# MCU.net
KiCad netlist of a schematic drawn in Altium Designer
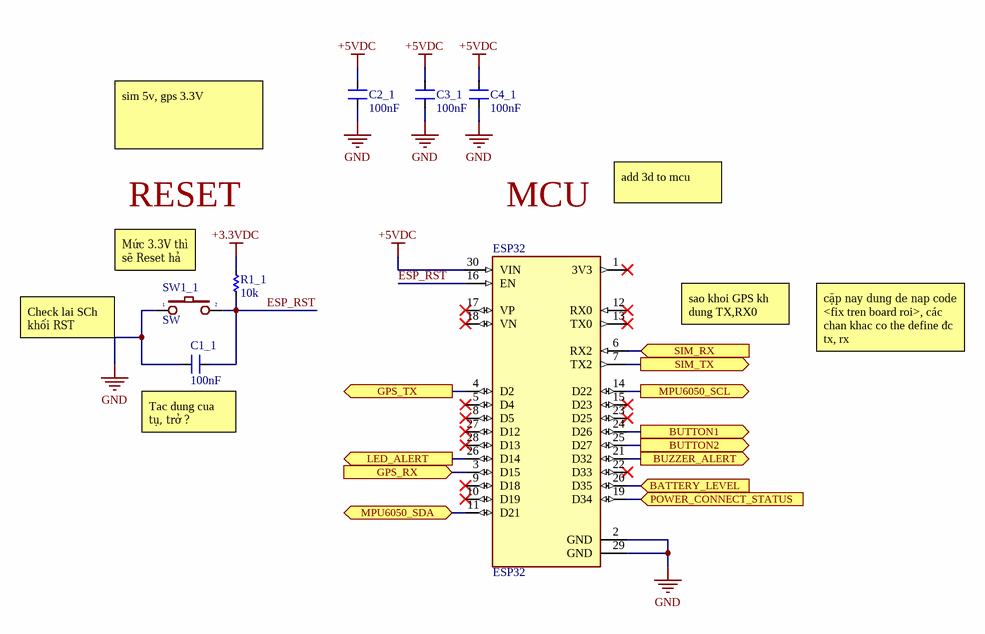
[diagram p0: MCU.SchDoc]

(export (version "E")
  (design (tool "Eeschema 10.0.6"))
  (components
    (comp (ref "C1_1")
      (value "100nF")
      (footprint "CN-SMD-0805")
      (libsource (lib "Altium Library") (part "CN"))
    )
    (comp (ref "C2_1")
      (value "100nF")
      (footprint "CN-SMD-0805")
      (libsource (lib "Altium Library") (part "CN"))
    )
    (comp (ref "C3_1")
      (value "100nF")
      (footprint "CN-SMD-0805")
      (libsource (lib "Altium Library") (part "CN"))
    )
    (comp (ref "C4_1")
      (value "100nF")
      (footprint "CN-SMD-0805")
      (libsource (lib "Altium Library") (part "CN"))
    )
    (comp (ref "ESP32")
      (value "ESP32")
      (footprint "MODULE_ESP32_DEVKIT_V1")
      (fields (field (name "MP") "ESP32-DEVKIT-V1"))
      (libsource (lib "GPS_LTE") (part "ESP32-DEVKIT-V1"))
    )
    (comp (ref "R1_1")
      (value "10k")
      (footprint "RES-SMD-0805")
      (description "Resistor")
      (fields
        (field (name "MANUFACTURER") "Generic Components")
        (field (name "PUBLISHER") "Altium Hobart Technology Centre")
      )
      (libsource (lib "Altium Library") (part "Res-SMD"))
    )
    (comp (ref "SW1_1")
      (value "SW")
      (footprint "SW1-DIP")
      (description "Switch button 2 pin")
      (libsource (lib "Altium Library") (part "SW2"))
    )
  )
  (nets
    (net (code "1") (name "+3.3VDC") (class "Default")
      (node (ref "R1_1") (pin "1") (pinfunction "1_1") (pintype "passive"))
    )
    (net (code "2") (name "+5VDC") (class "Default")
      (node (ref "C2_1") (pin "2") (pinfunction "2_2") (pintype "passive"))
      (node (ref "C3_1") (pin "2") (pinfunction "2_2") (pintype "passive"))
      (node (ref "C4_1") (pin "2") (pinfunction "2_2") (pintype "passive"))
      (node (ref "ESP32") (pin "30") (pinfunction "VIN_30") (pintype "input"))
    )
    (net (code "3") (name "/BATTERY_LEVEL") (class "Default")
      (node (ref "ESP32") (pin "20") (pinfunction "D35_20") (pintype "bidirectional"))
    )
    (net (code "4") (name "/BUTTON1") (class "Default")
      (node (ref "ESP32") (pin "24") (pinfunction "D26_24") (pintype "bidirectional"))
    )
    (net (code "5") (name "/BUTTON2") (class "Default")
      (node (ref "ESP32") (pin "25") (pinfunction "D27_25") (pintype "bidirectional"))
    )
    (net (code "6") (name "/BUZZER_ALERT") (class "Default")
      (node (ref "ESP32") (pin "21") (pinfunction "D32_21") (pintype "bidirectional"))
    )
    (net (code "7") (name "/ESP_RST") (class "Default")
      (node (ref "C1_1") (pin "2") (pinfunction "2_2") (pintype "passive"))
      (node (ref "ESP32") (pin "16") (pinfunction "EN_16") (pintype "input"))
      (node (ref "R1_1") (pin "2") (pinfunction "2_2") (pintype "passive"))
      (node (ref "SW1_1") (pin "2") (pinfunction "2_2") (pintype "passive"))
    )
    (net (code "8") (name "/GPS_RX") (class "Default")
      (node (ref "ESP32") (pin "3") (pinfunction "D15_3") (pintype "bidirectional"))
    )
    (net (code "9") (name "/GPS_TX") (class "Default")
      (node (ref "ESP32") (pin "4") (pinfunction "D2_4") (pintype "bidirectional"))
    )
    (net (code "10") (name "/LED_ALERT") (class "Default")
      (node (ref "ESP32") (pin "26") (pinfunction "D14_26") (pintype "bidirectional"))
    )
    (net (code "11") (name "/MPU6050_SCL") (class "Default")
      (node (ref "ESP32") (pin "14") (pinfunction "D22_14") (pintype "bidirectional"))
    )
    (net (code "12") (name "/MPU6050_SDA") (class "Default")
      (node (ref "ESP32") (pin "11") (pinfunction "D21_11") (pintype "bidirectional"))
    )
    (net (code "13") (name "/POWER_CONNECT_STATUS") (class "Default")
      (node (ref "ESP32") (pin "19") (pinfunction "D34_19") (pintype "bidirectional"))
    )
    (net (code "14") (name "/SIM_RX") (class "Default")
      (node (ref "ESP32") (pin "6") (pinfunction "RX2_6") (pintype "input"))
    )
    (net (code "15") (name "/SIM_TX") (class "Default")
      (node (ref "ESP32") (pin "7") (pinfunction "TX2_7") (pintype "output"))
    )
    (net (code "16") (name "GND") (class "Default")
      (node (ref "C1_1") (pin "1") (pinfunction "1_1") (pintype "passive"))
      (node (ref "C2_1") (pin "1") (pinfunction "1_1") (pintype "passive"))
      (node (ref "C3_1") (pin "1") (pinfunction "1_1") (pintype "passive"))
      (node (ref "C4_1") (pin "1") (pinfunction "1_1") (pintype "passive"))
      (node (ref "ESP32") (pin "2") (pinfunction "GND_2") (pintype "power_in"))
      (node (ref "ESP32") (pin "29") (pinfunction "GND_29") (pintype "power_in"))
      (node (ref "SW1_1") (pin "1") (pinfunction "1_1") (pintype "passive"))
    )
    (net (code "17") (name "unconnected-(ESP32-3V3-Pad1)") (class "Default")
      (node (ref "ESP32") (pin "1") (pinfunction "3V3_1") (pintype "output+no_connect"))
    )
    (net (code "18") (name "unconnected-(ESP32-D4-Pad5)") (class "Default")
      (node (ref "ESP32") (pin "5") (pinfunction "D4_5") (pintype "bidirectional+no_connect"))
    )
    (net (code "19") (name "unconnected-(ESP32-D5-Pad8)") (class "Default")
      (node (ref "ESP32") (pin "8") (pinfunction "D5_8") (pintype "bidirectional+no_connect"))
    )
    (net (code "20") (name "unconnected-(ESP32-D12-Pad27)") (class "Default")
      (node (ref "ESP32") (pin "27") (pinfunction "D12_27") (pintype "bidirectional+no_connect"))
    )
    (net (code "21") (name "unconnected-(ESP32-D13-Pad28)") (class "Default")
      (node (ref "ESP32") (pin "28") (pinfunction "D13_28") (pintype "bidirectional+no_connect"))
    )
    (net (code "22") (name "unconnected-(ESP32-D18-Pad9)") (class "Default")
      (node (ref "ESP32") (pin "9") (pinfunction "D18_9") (pintype "bidirectional+no_connect"))
    )
    (net (code "23") (name "unconnected-(ESP32-D19-Pad10)") (class "Default")
      (node (ref "ESP32") (pin "10") (pinfunction "D19_10") (pintype "bidirectional+no_connect"))
    )
    (net (code "24") (name "unconnected-(ESP32-D23-Pad15)") (class "Default")
      (node (ref "ESP32") (pin "15") (pinfunction "D23_15") (pintype "bidirectional+no_connect"))
    )
    (net (code "25") (name "unconnected-(ESP32-D25-Pad23)") (class "Default")
      (node (ref "ESP32") (pin "23") (pinfunction "D25_23") (pintype "bidirectional+no_connect"))
    )
    (net (code "26") (name "unconnected-(ESP32-D33-Pad22)") (class "Default")
      (node (ref "ESP32") (pin "22") (pinfunction "D33_22") (pintype "bidirectional+no_connect"))
    )
    (net (code "27") (name "unconnected-(ESP32-RX0-Pad12)") (class "Default")
      (node (ref "ESP32") (pin "12") (pinfunction "RX0_12") (pintype "input+no_connect"))
    )
    (net (code "28") (name "unconnected-(ESP32-TX0-Pad13)") (class "Default")
      (node (ref "ESP32") (pin "13") (pinfunction "TX0_13") (pintype "output+no_connect"))
    )
    (net (code "29") (name "unconnected-(ESP32-VN-Pad18)") (class "Default")
      (node (ref "ESP32") (pin "18") (pinfunction "VN_18") (pintype "bidirectional+no_connect"))
    )
    (net (code "30") (name "unconnected-(ESP32-VP-Pad17)") (class "Default")
      (node (ref "ESP32") (pin "17") (pinfunction "VP_17") (pintype "bidirectional+no_connect"))
    )
  )
)
